# CPU.net
KiCad netlist of a schematic drawn in Altium Designer
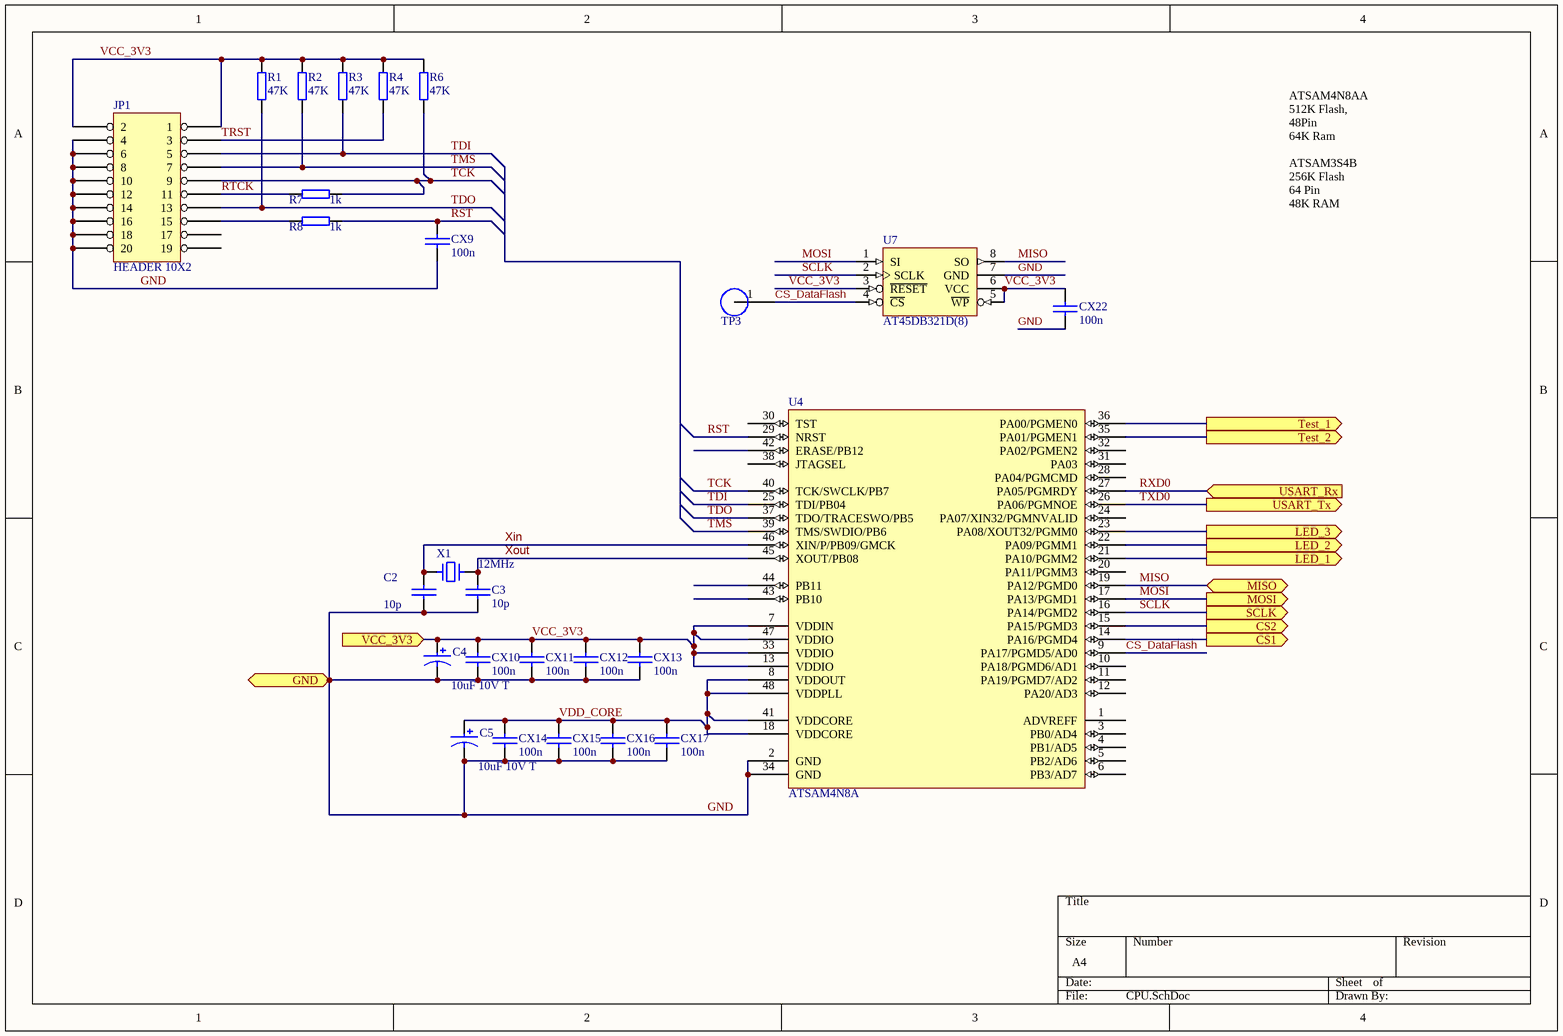
[diagram p0: CPU.SchDoc]

(export (version "E")
  (design (tool "Eeschema 10.0.6"))
  (components
    (comp (ref "C2") (value "10p") (footprint "0603") (libsource (lib "DEVICE") (part "CAP")))
    (comp (ref "C3") (value "10p") (footprint "0603") (libsource (lib "DEVICE") (part "CAP")))
    (comp (ref "C4")
      (value "10uF 10V T")
      (footprint "SMD-TANT-A")
      (libsource (lib "DEVICE") (part "CAPACITOR POL-S"))
    )
    (comp (ref "C5")
      (value "10uF 10V T")
      (footprint "SMD-TANT-A")
      (libsource (lib "DEVICE") (part "CAPACITOR POL-S"))
    )
    (comp (ref "CX9") (value "100n") (footprint "0603") (libsource (lib "D_LINEAR") (part "CAP")))
    (comp (ref "CX10") (value "100n") (footprint "0603") (libsource (lib "D_LINEAR") (part "CAP")))
    (comp (ref "CX11") (value "100n") (footprint "0603") (libsource (lib "D_LINEAR") (part "CAP")))
    (comp (ref "CX12") (value "100n") (footprint "0603") (libsource (lib "D_LINEAR") (part "CAP")))
    (comp (ref "CX13") (value "100n") (footprint "0603") (libsource (lib "D_LINEAR") (part "CAP")))
    (comp (ref "CX14") (value "100n") (footprint "0603") (libsource (lib "D_LINEAR") (part "CAP")))
    (comp (ref "CX15") (value "100n") (footprint "0603") (libsource (lib "D_LINEAR") (part "CAP")))
    (comp (ref "CX16") (value "100n") (footprint "0603") (libsource (lib "D_LINEAR") (part "CAP")))
    (comp (ref "CX17") (value "100n") (footprint "0603") (libsource (lib "D_LINEAR") (part "CAP")))
    (comp (ref "CX22") (value "100n") (footprint "0603") (libsource (lib "D_LINEAR") (part "CAP")))
    (comp (ref "JP1")
      (value "HEADER 10X2")
      (footprint "IDC20BOX")
      (libsource (lib "DEVICE") (part "HEADER 10X2"))
    )
    (comp (ref "R1") (value "47K") (footprint "0603") (libsource (lib "DEVICE") (part "RES8")))
    (comp (ref "R2") (value "47K") (footprint "0603") (libsource (lib "DEVICE") (part "RES8")))
    (comp (ref "R3") (value "47K") (footprint "0603") (libsource (lib "DEVICE") (part "RES8")))
    (comp (ref "R4") (value "47K") (footprint "0603") (libsource (lib "DEVICE") (part "RES8")))
    (comp (ref "R6") (value "47K") (footprint "0603") (libsource (lib "DEVICE") (part "RES8")))
    (comp (ref "R7") (value "1k") (footprint "0603") (libsource (lib "DEVICE") (part "RES8")))
    (comp (ref "R8") (value "1k") (footprint "0603") (libsource (lib "DEVICE") (part "RES8")))
    (comp (ref "TP3")
      (value "TestPad")
      (footprint "TestPad")
      (description "Test Pad")
      (libsource (lib "Hardware") (part "TestPad"))
    )
    (comp (ref "U4")
      (value "ATSAM4N8A")
      (footprint "48A_M")
      (description "Cortex-M4, 100MHz, 512K Flash, 64K SRAM")
      (libsource (lib "AtmelMicro") (part "ATSAM4N8A"))
    )
    (comp (ref "U7")
      (value "AT45DB321D(8)")
      (footprint "SO-8W-MLF")
      (libsource (lib "Atmel") (part "AT45DB041(8)"))
    )
    (comp (ref "X1") (value "12MHz") (footprint "XTAL-V2") (libsource (lib "DEVICE") (part "CRYSTAL")))
  )
  (nets
    (net (code "1") (name "/CS1") (class "Default")
      (node (ref "U4") (pin "14") (pinfunction "PA16/PGMD4_14") (pintype "bidirectional"))
    )
    (net (code "2") (name "/CS2") (class "Default")
      (node (ref "U4") (pin "15") (pinfunction "PA15/PGMD3_15") (pintype "bidirectional"))
    )
    (net (code "3") (name "/CS_DataFlash") (class "Default")
      (node (ref "TP3") (pin "1") (pintype "passive"))
      (node (ref "U4") (pin "9") (pinfunction "PA17/PGMD5/AD0_9") (pintype "bidirectional"))
      (node (ref "U7") (pin "4") (pinfunction "~{CS}_4") (pintype "input"))
    )
    (net (code "4") (name "/GND") (class "Default")
      (node (ref "C2") (pin "2") (pintype "passive"))
      (node (ref "C3") (pin "2") (pintype "passive"))
      (node (ref "C4") (pin "2") (pinfunction "2_2") (pintype "passive"))
      (node (ref "C5") (pin "2") (pinfunction "2_2") (pintype "passive"))
      (node (ref "CX10") (pin "1") (pintype "passive"))
      (node (ref "CX11") (pin "1") (pintype "passive"))
      (node (ref "CX12") (pin "1") (pintype "passive"))
      (node (ref "CX13") (pin "1") (pintype "passive"))
      (node (ref "CX14") (pin "1") (pintype "passive"))
      (node (ref "CX15") (pin "1") (pintype "passive"))
      (node (ref "CX16") (pin "1") (pintype "passive"))
      (node (ref "CX17") (pin "1") (pintype "passive"))
      (node (ref "CX22") (pin "1") (pintype "passive"))
      (node (ref "CX9") (pin "1") (pintype "passive"))
      (node (ref "JP1") (pin "10") (pinfunction "10_10") (pintype "passive"))
      (node (ref "JP1") (pin "12") (pinfunction "12_12") (pintype "passive"))
      (node (ref "JP1") (pin "14") (pinfunction "14_14") (pintype "passive"))
      (node (ref "JP1") (pin "16") (pinfunction "16_16") (pintype "passive"))
      (node (ref "JP1") (pin "18") (pinfunction "18_18") (pintype "passive"))
      (node (ref "JP1") (pin "20") (pinfunction "20_20") (pintype "passive"))
      (node (ref "JP1") (pin "4") (pinfunction "4_4") (pintype "passive"))
      (node (ref "JP1") (pin "6") (pinfunction "6_6") (pintype "passive"))
      (node (ref "JP1") (pin "8") (pinfunction "8_8") (pintype "passive"))
      (node (ref "U4") (pin "2") (pinfunction "GND_2") (pintype "power_in"))
      (node (ref "U4") (pin "34") (pinfunction "GND_34") (pintype "power_in"))
      (node (ref "U7") (pin "7") (pinfunction "GND_7") (pintype "power_in"))
    )
    (net (code "5") (name "/LED_1") (class "Default")
      (node (ref "U4") (pin "21") (pinfunction "PA10/PGMM2_21") (pintype "bidirectional"))
    )
    (net (code "6") (name "/LED_2") (class "Default")
      (node (ref "U4") (pin "22") (pinfunction "PA09/PGMM1_22") (pintype "bidirectional"))
    )
    (net (code "7") (name "/LED_3") (class "Default")
      (node (ref "U4") (pin "23") (pinfunction "PA08/XOUT32/PGMM0_23") (pintype "bidirectional"))
    )
    (net (code "8") (name "/MISO") (class "Default")
      (node (ref "U4") (pin "19") (pinfunction "PA12/PGMD0_19") (pintype "bidirectional"))
      (node (ref "U7") (pin "8") (pinfunction "SO_8") (pintype "output"))
    )
    (net (code "9") (name "/MOSI") (class "Default")
      (node (ref "U4") (pin "17") (pinfunction "PA13/PGMD1_17") (pintype "bidirectional"))
      (node (ref "U7") (pin "1") (pinfunction "SI_1") (pintype "input"))
    )
    (net (code "10") (name "/RST") (class "Default")
      (node (ref "CX9") (pin "2") (pintype "passive"))
      (node (ref "R8") (pin "2") (pintype "passive"))
      (node (ref "U4") (pin "29") (pinfunction "NRST_29") (pintype "bidirectional"))
    )
    (net (code "11") (name "/RTCK") (class "Default")
      (node (ref "JP1") (pin "11") (pinfunction "11_11") (pintype "passive"))
      (node (ref "R7") (pin "1") (pintype "passive"))
    )
    (net (code "12") (name "/RXD0") (class "Default")
      (node (ref "U4") (pin "27") (pinfunction "PA05/PGMRDY_27") (pintype "bidirectional"))
    )
    (net (code "13") (name "/SCLK") (class "Default")
      (node (ref "U4") (pin "16") (pinfunction "PA14/PGMD2_16") (pintype "bidirectional"))
      (node (ref "U7") (pin "2") (pinfunction "SCLK_2") (pintype "input"))
    )
    (net (code "14") (name "/TCK") (class "Default")
      (node (ref "JP1") (pin "9") (pinfunction "9_9") (pintype "passive"))
      (node (ref "R6") (pin "1") (pintype "passive"))
      (node (ref "R7") (pin "2") (pintype "passive"))
      (node (ref "U4") (pin "40") (pinfunction "TCK/SWCLK/PB7_40") (pintype "bidirectional"))
    )
    (net (code "15") (name "/TDI") (class "Default")
      (node (ref "JP1") (pin "5") (pinfunction "5_5") (pintype "passive"))
      (node (ref "R3") (pin "1") (pintype "passive"))
      (node (ref "U4") (pin "25") (pinfunction "TDI/PB04_25") (pintype "bidirectional"))
    )
    (net (code "16") (name "/TDO") (class "Default")
      (node (ref "JP1") (pin "13") (pinfunction "13_13") (pintype "passive"))
      (node (ref "R1") (pin "1") (pintype "passive"))
      (node (ref "U4") (pin "37") (pinfunction "TDO/TRACESWO/PB5_37") (pintype "bidirectional"))
    )
    (net (code "17") (name "/TMS") (class "Default")
      (node (ref "JP1") (pin "7") (pinfunction "7_7") (pintype "passive"))
      (node (ref "R2") (pin "1") (pintype "passive"))
      (node (ref "U4") (pin "39") (pinfunction "TMS/SWDIO/PB6_39") (pintype "bidirectional"))
    )
    (net (code "18") (name "/TRST") (class "Default")
      (node (ref "JP1") (pin "3") (pinfunction "3_3") (pintype "passive"))
      (node (ref "R4") (pin "1") (pintype "passive"))
    )
    (net (code "19") (name "/TXD0") (class "Default")
      (node (ref "U4") (pin "26") (pinfunction "PA06/PGMNOE_26") (pintype "bidirectional"))
    )
    (net (code "20") (name "/Test_1") (class "Default")
      (node (ref "U4") (pin "36") (pinfunction "PA00/PGMEN0_36") (pintype "bidirectional"))
    )
    (net (code "21") (name "/Test_2") (class "Default")
      (node (ref "U4") (pin "35") (pinfunction "PA01/PGMEN1_35") (pintype "bidirectional"))
    )
    (net (code "22") (name "/VCC_3V3") (class "Default")
      (node (ref "C4") (pin "1") (pinfunction "1_1") (pintype "passive"))
      (node (ref "CX10") (pin "2") (pintype "passive"))
      (node (ref "CX11") (pin "2") (pintype "passive"))
      (node (ref "CX12") (pin "2") (pintype "passive"))
      (node (ref "CX13") (pin "2") (pintype "passive"))
      (node (ref "CX22") (pin "2") (pintype "passive"))
      (node (ref "JP1") (pin "1") (pinfunction "1_1") (pintype "passive"))
      (node (ref "JP1") (pin "2") (pinfunction "2_2") (pintype "passive"))
      (node (ref "R1") (pin "2") (pintype "passive"))
      (node (ref "R2") (pin "2") (pintype "passive"))
      (node (ref "R3") (pin "2") (pintype "passive"))
      (node (ref "R4") (pin "2") (pintype "passive"))
      (node (ref "R6") (pin "2") (pintype "passive"))
      (node (ref "U4") (pin "13") (pinfunction "VDDIO_13") (pintype "power_in"))
      (node (ref "U4") (pin "33") (pinfunction "VDDIO_33") (pintype "power_in"))
      (node (ref "U4") (pin "47") (pinfunction "VDDIO_47") (pintype "power_in"))
      (node (ref "U4") (pin "7") (pinfunction "VDDIN_7") (pintype "power_in"))
      (node (ref "U7") (pin "3") (pinfunction "~{RESET}_3") (pintype "input"))
      (node (ref "U7") (pin "5") (pinfunction "~{WP}_5") (pintype "input"))
      (node (ref "U7") (pin "6") (pinfunction "VCC_6") (pintype "power_in"))
    )
    (net (code "23") (name "/VDD_CORE") (class "Default")
      (node (ref "C5") (pin "1") (pinfunction "1_1") (pintype "passive"))
      (node (ref "CX14") (pin "2") (pintype "passive"))
      (node (ref "CX15") (pin "2") (pintype "passive"))
      (node (ref "CX16") (pin "2") (pintype "passive"))
      (node (ref "CX17") (pin "2") (pintype "passive"))
      (node (ref "U4") (pin "18") (pinfunction "VDDCORE_18") (pintype "power_in"))
      (node (ref "U4") (pin "41") (pinfunction "VDDCORE_41") (pintype "power_in"))
      (node (ref "U4") (pin "48") (pinfunction "VDDPLL_48") (pintype "power_in"))
      (node (ref "U4") (pin "8") (pinfunction "VDDOUT_8") (pintype "power_in"))
    )
    (net (code "24") (name "/Xin") (class "Default")
      (node (ref "C2") (pin "1") (pintype "passive"))
      (node (ref "U4") (pin "46") (pinfunction "XIN/P/PB09/GMCK_46") (pintype "bidirectional"))
      (node (ref "X1") (pin "2") (pintype "passive"))
    )
    (net (code "25") (name "/Xout") (class "Default")
      (node (ref "C3") (pin "1") (pintype "passive"))
      (node (ref "U4") (pin "45") (pinfunction "XOUT/PB08_45") (pintype "bidirectional"))
      (node (ref "X1") (pin "1") (pintype "passive"))
    )
    (net (code "26") (name "Net-(JP1-Pad15)") (class "Default")
      (node (ref "JP1") (pin "15") (pinfunction "15_15") (pintype "passive"))
      (node (ref "R8") (pin "1") (pintype "passive"))
    )
    (net (code "27") (name "unconnected-(JP1-Pad17)") (class "Default")
      (node (ref "JP1") (pin "17") (pinfunction "17_17") (pintype "passive"))
    )
    (net (code "28") (name "unconnected-(JP1-Pad19)") (class "Default")
      (node (ref "JP1") (pin "19") (pinfunction "19_19") (pintype "passive"))
    )
    (net (code "29") (name "unconnected-(U4-ADVREFF-Pad1)") (class "Default")
      (node (ref "U4") (pin "1") (pinfunction "ADVREFF_1") (pintype "tri_state"))
    )
    (net (code "30") (name "unconnected-(U4-ERASE{slash}PB12-Pad42)") (class "Default")
      (node (ref "U4") (pin "42") (pinfunction "ERASE/PB12_42") (pintype "bidirectional"))
    )
    (net (code "31") (name "unconnected-(U4-JTAGSEL-Pad38)") (class "Default")
      (node (ref "U4") (pin "38") (pinfunction "JTAGSEL_38") (pintype "bidirectional"))
    )
    (net (code "32") (name "unconnected-(U4-PA02{slash}PGMEN2-Pad32)") (class "Default")
      (node (ref "U4") (pin "32") (pinfunction "PA02/PGMEN2_32") (pintype "bidirectional"))
    )
    (net (code "33") (name "unconnected-(U4-PA03-Pad31)") (class "Default")
      (node (ref "U4") (pin "31") (pinfunction "PA03_31") (pintype "bidirectional"))
    )
    (net (code "34") (name "unconnected-(U4-PA04{slash}PGMCMD-Pad28)") (class "Default")
      (node (ref "U4") (pin "28") (pinfunction "PA04/PGMCMD_28") (pintype "bidirectional"))
    )
    (net (code "35") (name "unconnected-(U4-PA07{slash}XIN32{slash}PGMNVALID-Pad24)") (class "Default")
      (node (ref "U4") (pin "24") (pinfunction "PA07/XIN32/PGMNVALID_24") (pintype "bidirectional"))
    )
    (net (code "36") (name "unconnected-(U4-PA11{slash}PGMM3-Pad20)") (class "Default")
      (node (ref "U4") (pin "20") (pinfunction "PA11/PGMM3_20") (pintype "bidirectional"))
    )
    (net (code "37") (name "unconnected-(U4-PA18{slash}PGMD6{slash}AD1-Pad10)") (class "Default")
      (node (ref "U4") (pin "10") (pinfunction "PA18/PGMD6/AD1_10") (pintype "bidirectional"))
    )
    (net (code "38") (name "unconnected-(U4-PA19{slash}PGMD7{slash}AD2-Pad11)") (class "Default")
      (node (ref "U4") (pin "11") (pinfunction "PA19/PGMD7/AD2_11") (pintype "bidirectional"))
    )
    (net (code "39") (name "unconnected-(U4-PA20{slash}AD3-Pad12)") (class "Default")
      (node (ref "U4") (pin "12") (pinfunction "PA20/AD3_12") (pintype "bidirectional"))
    )
    (net (code "40") (name "unconnected-(U4-PB0{slash}AD4-Pad3)") (class "Default")
      (node (ref "U4") (pin "3") (pinfunction "PB0/AD4_3") (pintype "bidirectional"))
    )
    (net (code "41") (name "unconnected-(U4-PB1{slash}AD5-Pad4)") (class "Default")
      (node (ref "U4") (pin "4") (pinfunction "PB1/AD5_4") (pintype "bidirectional"))
    )
    (net (code "42") (name "unconnected-(U4-PB2{slash}AD6-Pad5)") (class "Default")
      (node (ref "U4") (pin "5") (pinfunction "PB2/AD6_5") (pintype "bidirectional"))
    )
    (net (code "43") (name "unconnected-(U4-PB3{slash}AD7-Pad6)") (class "Default")
      (node (ref "U4") (pin "6") (pinfunction "PB3/AD7_6") (pintype "bidirectional"))
    )
    (net (code "44") (name "unconnected-(U4-PB10-Pad43)") (class "Default")
      (node (ref "U4") (pin "43") (pinfunction "PB10_43") (pintype "bidirectional"))
    )
    (net (code "45") (name "unconnected-(U4-PB11-Pad44)") (class "Default")
      (node (ref "U4") (pin "44") (pinfunction "PB11_44") (pintype "bidirectional"))
    )
    (net (code "46") (name "unconnected-(U4-TST-Pad30)") (class "Default")
      (node (ref "U4") (pin "30") (pinfunction "TST_30") (pintype "bidirectional"))
    )
  )
)
